# 21-RGMII_ETHERNET_PHY_-_ICSSG_PRG2_PRU1.net
KiCad netlist of a schematic drawn in Altium Designer
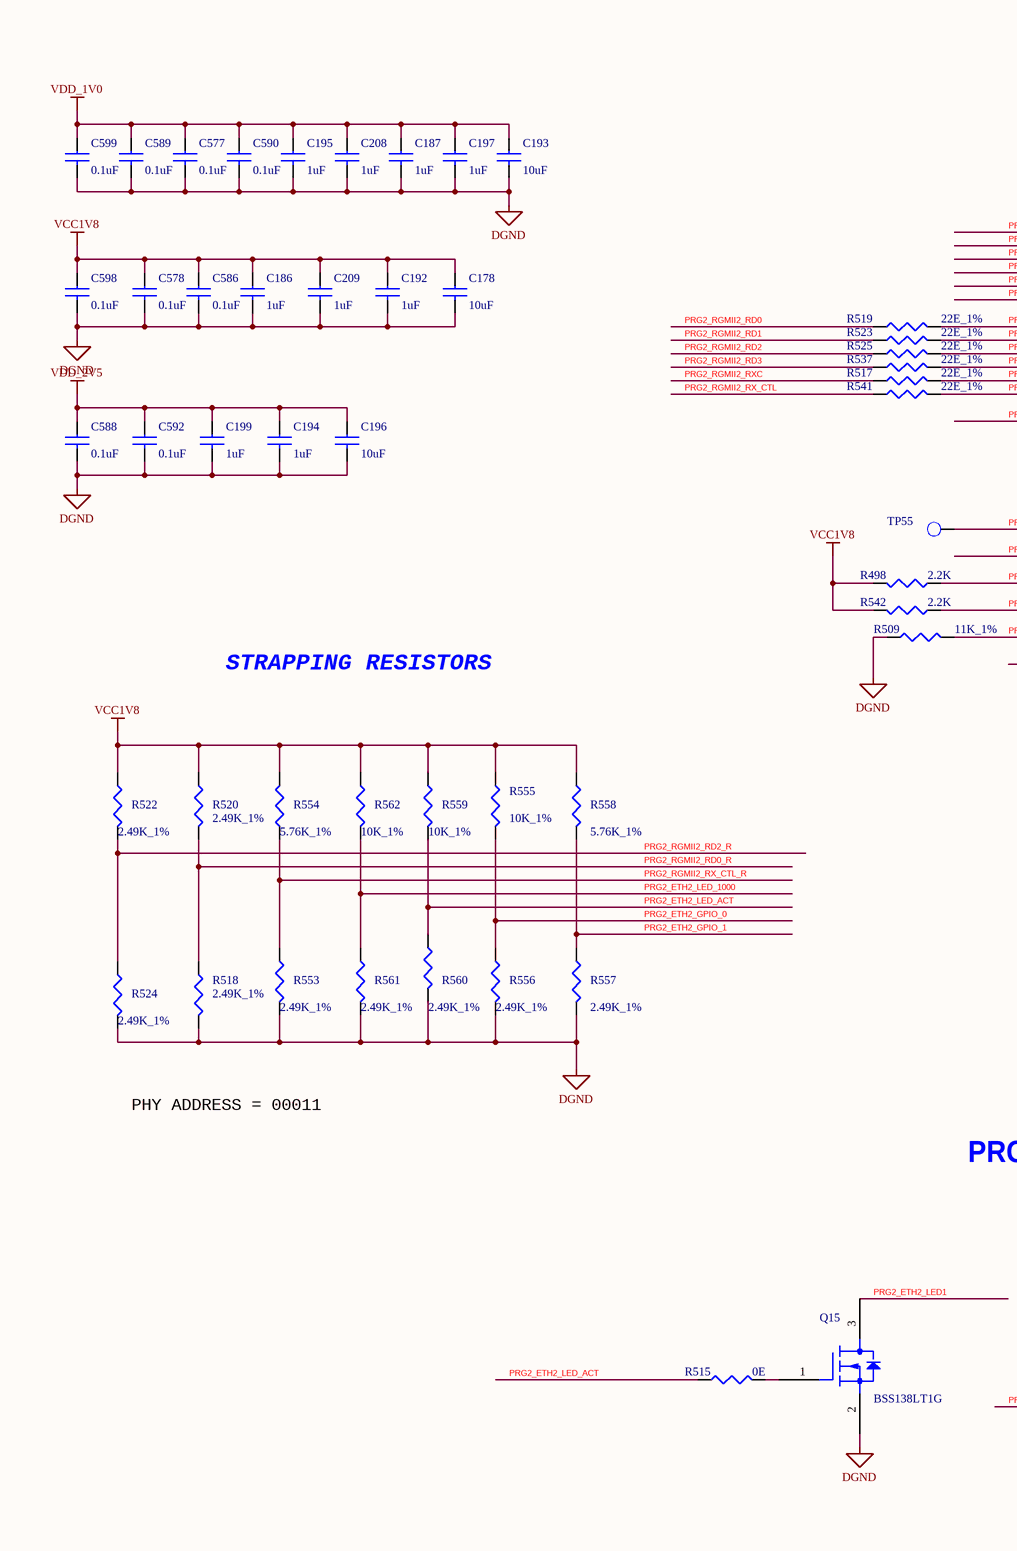
[diagram p0: 21-RGMII ETHERNET PHY - ICSSG PRG2_PRU1.SchDoc, left]
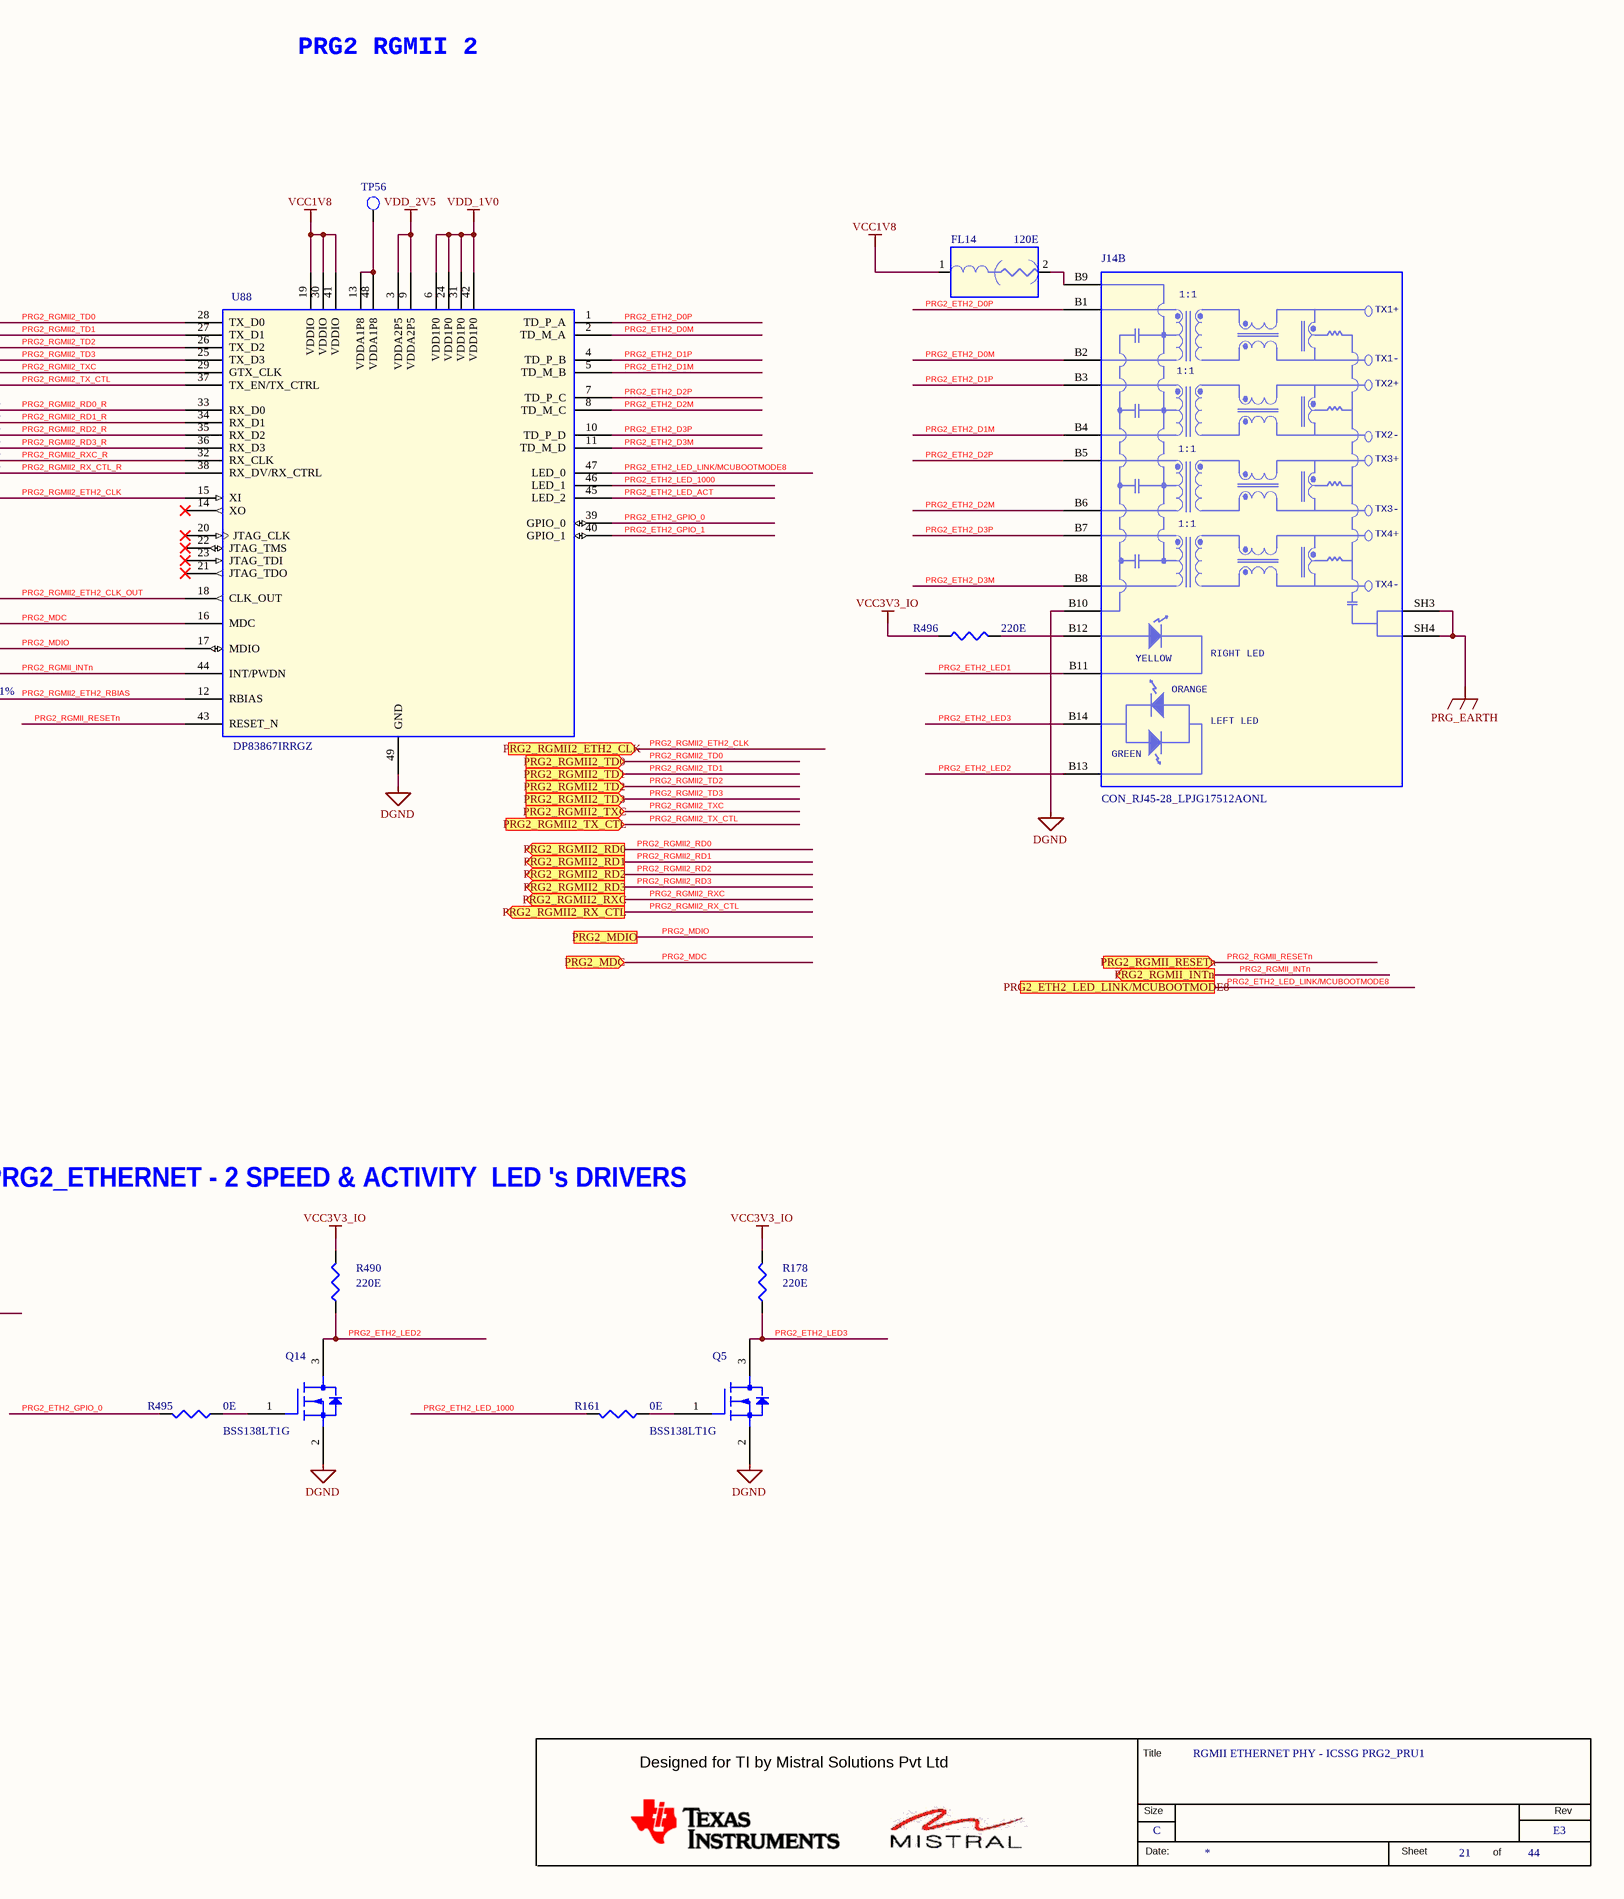
[diagram p1: 21-RGMII ETHERNET PHY - ICSSG PRG2_PRU1.SchDoc, right]

(export (version "E")
  (design (tool "Eeschema 10.0.6"))
  (components
    (comp (ref "C178")
      (value "10uF")
      (footprint "CAP0603_1")
      (description "CAP CERAMIC 10uF 10V 10% X5R 0603")
      (fields (field (name "DISTRIBUTOR_PART_NUMBER") "478-10766-1-ND") (field (name "VOLTAGE") "10V"))
      (libsource (lib "*") (part "CAP_Dup5"))
    )
    (comp (ref "C186")
      (value "1uF")
      (footprint "CAP0402_0-75")
      (description "CAP CERAMIC 1uF 16V 20% X5R 0402")
      (fields (field (name "DISTRIBUTOR_PART_NUMBER") "587-5514-1-ND") (field (name "VOLTAGE") "16V"))
      (libsource (lib "*") (part "CAP_Dup5"))
    )
    (comp (ref "C187")
      (value "1uF")
      (footprint "CAP0402_0-75")
      (description "CAP CERAMIC 1uF 16V 20% X5R 0402")
      (fields
        (field (name "MISTRAL PART NO") "120018020006-R")
        (field (name "MFR_PART_NUMBER") "EMK105BJ105MV-F")
      )
      (libsource (lib "*") (part "CAP_Dup5"))
    )
    (comp (ref "C192")
      (value "1uF")
      (footprint "CAP0402_0-75")
      (description "CAP CERAMIC 1uF 16V 20% X5R 0402")
      (fields (field (name "DISTRIBUTOR_PART_NUMBER") "587-5514-1-ND") (field (name "VOLTAGE") "16V"))
      (libsource (lib "*") (part "CAP_Dup5"))
    )
    (comp (ref "C193")
      (value "10uF")
      (footprint "CAP0603_1")
      (description "CAP CERAMIC 10uF 10V 10% X5R 0603")
      (fields
        (field (name "MISTRAL PART NO") "120010080001-R")
        (field (name "MFR_PART_NUMBER") "0603ZD106KAT2A")
      )
      (libsource (lib "*") (part "CAP_Dup5"))
    )
    (comp (ref "C194")
      (value "1uF")
      (footprint "CAP0402_0-75")
      (description "CAP CERAMIC 1uF 16V 20% X5R 0402")
      (fields
        (field (name "MISTRAL PART NO") "120018020006-R")
        (field (name "MFR_PART_NUMBER") "EMK105BJ105MV-F")
      )
      (libsource (lib "*") (part "CAP_Dup5"))
    )
    (comp (ref "C195")
      (value "1uF")
      (footprint "CAP0402_0-75")
      (description "CAP CERAMIC 1uF 16V 20% X5R 0402")
      (fields
        (field (name "MISTRAL PART NO") "120018020006-R")
        (field (name "MFR_PART_NUMBER") "EMK105BJ105MV-F")
      )
      (libsource (lib "*") (part "CAP_Dup5"))
    )
    (comp (ref "C196")
      (value "10uF")
      (footprint "CAP0603_1")
      (description "CAP CERAMIC 10uF 10V 10% X5R 0603")
      (fields
        (field (name "MISTRAL PART NO") "120010080001-R")
        (field (name "MFR_PART_NUMBER") "0603ZD106KAT2A")
      )
      (libsource (lib "*") (part "CAP_Dup5"))
    )
    (comp (ref "C197")
      (value "1uF")
      (footprint "CAP0402_0-75")
      (description "CAP CERAMIC 1uF 16V 20% X5R 0402")
      (fields (field (name "DISTRIBUTOR_PART_NUMBER") "587-5514-1-ND") (field (name "VOLTAGE") "16V"))
      (libsource (lib "*") (part "CAP_Dup5"))
    )
    (comp (ref "C199")
      (value "1uF")
      (footprint "CAP0402_0-75")
      (description "CAP CERAMIC 1uF 16V 20% X5R 0402")
      (fields
        (field (name "MISTRAL PART NO") "120018020006-R")
        (field (name "MFR_PART_NUMBER") "EMK105BJ105MV-F")
      )
      (libsource (lib "*") (part "CAP_Dup5"))
    )
    (comp (ref "C208")
      (value "1uF")
      (footprint "CAP0402_0-75")
      (description "CAP CERAMIC 1uF 16V 20% X5R 0402")
      (fields (field (name "DISTRIBUTOR_PART_NUMBER") "587-5514-1-ND") (field (name "VOLTAGE") "16V"))
      (libsource (lib "*") (part "CAP_Dup5"))
    )
    (comp (ref "C209")
      (value "1uF")
      (footprint "CAP0402_0-75")
      (description "CAP CERAMIC 1uF 16V 20% X5R 0402")
      (fields (field (name "DISTRIBUTOR_PART_NUMBER") "587-5514-1-ND") (field (name "VOLTAGE") "16V"))
      (libsource (lib "*") (part "CAP_Dup5"))
    )
    (comp (ref "C577")
      (value "0.1uF")
      (footprint "CAP0201_0-5")
      (description "CAP CERAMIC 0.1uF 16V 10% X5R 0201")
      (fields (field (name "DISTRIBUTOR_PART_NUMBER") "490-16742-1-ND") (field (name "VOLTAGE") "16V"))
      (libsource (lib "*") (part "CAP_Dup5"))
    )
    (comp (ref "C578")
      (value "0.1uF")
      (footprint "CAP0201_0-5")
      (description "CAP CERAMIC 0.1uF 16V 10% X5R 0201")
      (fields (field (name "DISTRIBUTOR_PART_NUMBER") "490-16742-1-ND") (field (name "VOLTAGE") "16V"))
      (libsource (lib "*") (part "CAP_Dup5"))
    )
    (comp (ref "C586")
      (value "0.1uF")
      (footprint "CAP0201_0-5")
      (description "CAP CERAMIC 0.1uF 16V 10% X5R 0201")
      (fields (field (name "DISTRIBUTOR_PART_NUMBER") "490-16742-1-ND") (field (name "VOLTAGE") "16V"))
      (libsource (lib "*") (part "CAP_Dup5"))
    )
    (comp (ref "C588")
      (value "0.1uF")
      (footprint "CAP0201_0-5")
      (description "CAP CERAMIC 0.1uF 16V 10% X5R 0201")
      (fields
        (field (name "MISTRAL PART NO") "120009030072-R")
        (field (name "MFR_PART_NUMBER") "GRM033R61C104KE84J")
      )
      (libsource (lib "*") (part "CAP_Dup5"))
    )
    (comp (ref "C589")
      (value "0.1uF")
      (footprint "CAP0201_0-5")
      (description "CAP CERAMIC 0.1uF 16V 10% X5R 0201")
      (fields
        (field (name "MISTRAL PART NO") "120009030072-R")
        (field (name "MFR_PART_NUMBER") "GRM033R61C104KE84J")
      )
      (libsource (lib "*") (part "CAP_Dup5"))
    )
    (comp (ref "C590")
      (value "0.1uF")
      (footprint "CAP0201_0-5")
      (description "CAP CERAMIC 0.1uF 16V 10% X5R 0201")
      (fields (field (name "DISTRIBUTOR_PART_NUMBER") "490-16742-1-ND") (field (name "VOLTAGE") "16V"))
      (libsource (lib "*") (part "CAP_Dup5"))
    )
    (comp (ref "C592")
      (value "0.1uF")
      (footprint "CAP0201_0-5")
      (description "CAP CERAMIC 0.1uF 16V 10% X5R 0201")
      (fields (field (name "DISTRIBUTOR_PART_NUMBER") "490-16742-1-ND") (field (name "VOLTAGE") "16V"))
      (libsource (lib "*") (part "CAP_Dup5"))
    )
    (comp (ref "C598")
      (value "0.1uF")
      (footprint "CAP0201_0-5")
      (description "CAP CERAMIC 0.1uF 16V 10% X5R 0201")
      (fields (field (name "DISTRIBUTOR_PART_NUMBER") "490-16742-1-ND") (field (name "VOLTAGE") "16V"))
      (libsource (lib "*") (part "CAP_Dup5"))
    )
    (comp (ref "C599")
      (value "0.1uF")
      (footprint "CAP0201_0-5")
      (description "CAP CERAMIC 0.1uF 16V 10% X5R 0201")
      (fields
        (field (name "MISTRAL PART NO") "120009030072-R")
        (field (name "MFR_PART_NUMBER") "GRM033R61C104KE84J")
      )
      (libsource (lib "*") (part "CAP_Dup5"))
    )
    (comp (ref "FL14")
      (value "120E")
      (footprint "EMIFIL_BLM15A_0402_0-6")
      (description "FERRITE CHIP 120E 1.3A 0402")
      (fields (field (name "DISTRIBUTOR_PART_NUMBER") "490-5203-1-ND") (field (name "VOLTAGE") "NA"))
      (libsource (lib "*") (part "EMIFILTER_IND"))
    )
    (comp (ref "J14")
      (value "CON_RJ45-28_LPJG17512AONL")
      (footprint "CON_RJ45-28_LPJG17512_S_R_T_25-3")
      (description "CON JACK RJ45 28POS REGISTERED FEMALE RA TH")
      (fields
        (field (name "MISTRAL PART NO") "150017080001-R")
        (field (name "MFR_PART_NUMBER") "LPJG17512AONL")
      )
      (libsource (lib "*") (part "CON_RJ45-28_LPJG17512AONL"))
    )
    (comp (ref "Q5")
      (value "BSS138LT1G")
      (footprint "SOT23-123")
      (description "IC MOSFET N-CHANNEL 50V, SOT23-3")
      (fields (field (name "DISTRIBUTOR_PART_NUMBER") "863-BSS138LT1G") (field (name "VOLTAGE") "50V"))
      (libsource (lib "*") (part "MOSFET_BSS138LT1G"))
    )
    (comp (ref "Q14")
      (value "BSS138LT1G")
      (footprint "SOT23-123")
      (description "IC MOSFET N-CHANNEL 50V, SOT23-3")
      (fields (field (name "MISTRAL PART NO") "142016040001-R") (field (name "TOLERANCE") "NA"))
      (libsource (lib "*") (part "MOSFET_BSS138LT1G"))
    )
    (comp (ref "Q15")
      (value "BSS138LT1G")
      (footprint "SOT23-123")
      (description "IC MOSFET N-CHANNEL 50V, SOT23-3")
      (fields (field (name "DISTRIBUTOR_PART_NUMBER") "863-BSS138LT1G") (field (name "VOLTAGE") "50V"))
      (libsource (lib "*") (part "MOSFET_BSS138LT1G"))
    )
    (comp (ref "R161")
      (value "0E")
      (footprint "RES0402_0-5")
      (description "RES 0E 1/16W 0402")
      (fields (field (name "DISTRIBUTOR_PART_NUMBER") "541-0.0JCT-ND") (field (name "VOLTAGE") "NA"))
      (libsource (lib "*") (part "RESISTOR_Dup4"))
    )
    (comp (ref "R178")
      (value "220E")
      (footprint "RES0402_0-5")
      (description "RES 220E 1/16W 5% 0402")
      (fields (field (name "VOLTAGE") "NA") (field (name "DISTRIBUTOR_PART_NUMBER") "P220JCT-ND"))
      (libsource (lib "*") (part "RESISTOR_Dup5"))
    )
    (comp (ref "R490")
      (value "220E")
      (footprint "RES0402_0-5")
      (description "RES 220E 1/16W 5% 0402")
      (fields (field (name "VOLTAGE") "NA") (field (name "MISTRAL PART NO") "110009030506-R"))
      (libsource (lib "*") (part "RESISTOR_Dup5"))
    )
    (comp (ref "R495")
      (value "0E")
      (footprint "RES0402_0-5")
      (description "RES 0E 1/16W 0402")
      (fields
        (field (name "MISTRAL PART NO") "110010080019-P")
        (field (name "MFR_PART_NUMBER") "CRCW04020000Z0ED")
      )
      (libsource (lib "*") (part "RESISTOR_Dup4"))
    )
    (comp (ref "R496")
      (value "220E")
      (footprint "RES0402_0-5")
      (description "RES 220E 1/16W 5% 0402")
      (fields (field (name "VOLTAGE") "NA") (field (name "DISTRIBUTOR_PART_NUMBER") "P220JCT-ND"))
      (libsource (lib "*") (part "RESISTOR_Dup5"))
    )
    (comp (ref "R498")
      (value "2.2K")
      (footprint "RES0402_0-5")
      (description "RES 2.2K 1/16W 5% 0402")
      (fields (field (name "DISTRIBUTOR_PART_NUMBER") "311-2.2KJRCT-ND") (field (name "VOLTAGE") "NA"))
      (libsource (lib "*") (part "RESISTOR_Dup5"))
    )
    (comp (ref "R509")
      (value "11K_1%")
      (footprint "RES0402_0-5")
      (description "RES 11K 1/16W 1% 0402")
      (fields (field (name "DISTRIBUTOR_PART_NUMBER") "311-11.0KLRCT-ND") (field (name "VOLTAGE") "NA"))
      (libsource (lib "*") (part "RESISTOR_Dup5"))
    )
    (comp (ref "R515")
      (value "0E")
      (footprint "RES0402_0-5")
      (description "RES 0E 1/16W 0402")
      (fields (field (name "DISTRIBUTOR_PART_NUMBER") "541-0.0JCT-ND") (field (name "VOLTAGE") "NA"))
      (libsource (lib "*") (part "RESISTOR_Dup4"))
    )
    (comp (ref "R517")
      (value "22E_1%")
      (footprint "RES0402")
      (description "RES 22E 1/16W 1% 0402")
      (fields
        (field (name "MISTRAL PART NO") "110009090004-P")
        (field (name "MFR_PART_NUMBER") "RC0402FR-0722RL")
      )
      (libsource (lib "*") (part "RESISTOR_Dup5"))
    )
    (comp (ref "R518")
      (value "2.49K_1%")
      (footprint "RES0402")
      (description "RES 2.49K 1/16W 1% 0402")
      (fields (field (name "DISTRIBUTOR_PART_NUMBER") "311-2.49KLRCT-ND") (field (name "VOLTAGE") "NA"))
      (libsource (lib "*") (part "RESISTOR_Dup5"))
    )
    (comp (ref "R519")
      (value "22E_1%")
      (footprint "RES0402")
      (description "RES 22E 1/16W 1% 0402")
      (fields
        (field (name "CUST_PART_NUMBER") "4700-80047E")
        (field (name "DISTRIBUTOR_PART_NUMBER") "311-22.0LRCT-ND")
      )
      (libsource (lib "*") (part "RESISTOR_Dup5"))
    )
    (comp (ref "R520")
      (value "2.49K_1%")
      (footprint "RES0402")
      (description "RES 2.49K 1/16W 1% 0402")
      (fields
        (field (name "MISTRAL PART NO") "110016050020-R")
        (field (name "MFR_PART_NUMBER") "RC0402FR-072K49L")
      )
      (libsource (lib "*") (part "RESISTOR_Dup5"))
    )
    (comp (ref "R522")
      (value "2.49K_1%")
      (footprint "RES0402")
      (description "RES 2.49K 1/16W 1% 0402")
      (fields (field (name "DISTRIBUTOR_PART_NUMBER") "311-2.49KLRCT-ND") (field (name "VOLTAGE") "NA"))
      (libsource (lib "*") (part "RESISTOR_Dup5"))
    )
    (comp (ref "R523")
      (value "22E_1%")
      (footprint "RES0402")
      (description "RES 22E 1/16W 1% 0402")
      (fields
        (field (name "MISTRAL PART NO") "110009090004-P")
        (field (name "MFR_PART_NUMBER") "RC0402FR-0722RL")
      )
      (libsource (lib "*") (part "RESISTOR_Dup5"))
    )
    (comp (ref "R524")
      (value "2.49K_1%")
      (footprint "RES0402")
      (description "RES 2.49K 1/16W 1% 0402")
      (fields (field (name "DISTRIBUTOR_PART_NUMBER") "311-2.49KLRCT-ND") (field (name "VOLTAGE") "NA"))
      (libsource (lib "*") (part "RESISTOR_Dup5"))
    )
    (comp (ref "R525")
      (value "22E_1%")
      (footprint "RES0402")
      (description "RES 22E 1/16W 1% 0402")
      (fields
        (field (name "CUST_PART_NUMBER") "4700-80047E")
        (field (name "DISTRIBUTOR_PART_NUMBER") "311-22.0LRCT-ND")
      )
      (libsource (lib "*") (part "RESISTOR_Dup5"))
    )
    (comp (ref "R537")
      (value "22E_1%")
      (footprint "RES0402")
      (description "RES 22E 1/16W 1% 0402")
      (fields
        (field (name "MISTRAL PART NO") "110009090004-P")
        (field (name "MFR_PART_NUMBER") "RC0402FR-0722RL")
      )
      (libsource (lib "*") (part "RESISTOR_Dup5"))
    )
    (comp (ref "R541")
      (value "22E_1%")
      (footprint "RES0402")
      (description "RES 22E 1/16W 1% 0402")
      (fields
        (field (name "CUST_PART_NUMBER") "4700-80047E")
        (field (name "DISTRIBUTOR_PART_NUMBER") "311-22.0LRCT-ND")
      )
      (libsource (lib "*") (part "RESISTOR_Dup5"))
    )
    (comp (ref "R542")
      (value "2.2K")
      (footprint "RES0402_0-5")
      (description "RES 2.2K 1/16W 5% 0402")
      (fields
        (field (name "MISTRAL PART NO") "110010120018-R")
        (field (name "MFR_PART_NUMBER") "RC0402JR-072K2L")
      )
      (libsource (lib "*") (part "RESISTOR_Dup5"))
    )
    (comp (ref "R553")
      (value "2.49K_1%")
      (footprint "RES0402")
      (description "RES 2.49K 1/16W 1% 0402")
      (fields (field (name "DISTRIBUTOR_PART_NUMBER") "311-2.49KLRCT-ND") (field (name "VOLTAGE") "NA"))
      (libsource (lib "*") (part "RESISTOR_Dup5"))
    )
    (comp (ref "R554")
      (value "5.76K_1%")
      (footprint "RES0402")
      (description "RES 5.76K 1/10W 1% 0402")
      (fields
        (field (name "MISTRAL PART NO") "110009030945-R")
        (field (name "MFR_PART_NUMBER") "ERJ-2RKF5761X")
      )
      (libsource (lib "*") (part "RESISTOR_Dup5"))
    )
    (comp (ref "R555")
      (value "10K_1%")
      (footprint "RES0402_0-5")
      (description "RES 10K 1/16W 1% 0402")
      (fields
        (field (name "MISTRAL PART NO") "110009030220-P")
        (field (name "MFR_PART_NUMBER") "RC0402FR-0710KL")
      )
      (libsource (lib "*") (part "RESISTOR_Dup5"))
    )
    (comp (ref "R556")
      (value "2.49K_1%")
      (footprint "RES0402")
      (description "RES 2.49K 1/16W 1% 0402")
      (fields
        (field (name "MISTRAL PART NO") "110016050020-R")
        (field (name "MFR_PART_NUMBER") "RC0402FR-072K49L")
      )
      (libsource (lib "*") (part "RESISTOR_Dup5"))
    )
    (comp (ref "R557")
      (value "2.49K_1%")
      (footprint "RES0402")
      (description "RES 2.49K 1/16W 1% 0402")
      (fields
        (field (name "MISTRAL PART NO") "110016050020-R")
        (field (name "MFR_PART_NUMBER") "RC0402FR-072K49L")
      )
      (libsource (lib "*") (part "RESISTOR_Dup5"))
    )
    (comp (ref "R558")
      (value "5.76K_1%")
      (footprint "RES0402")
      (description "RES 5.76K 1/10W 1% 0402")
      (fields (field (name "DISTRIBUTOR_PART_NUMBER") "P5.76KLCT-ND") (field (name "TOLERANCE") "1%"))
      (libsource (lib "*") (part "RESISTOR_Dup5"))
    )
    (comp (ref "R559")
      (value "10K_1%")
      (footprint "RES0402_0-5")
      (description "RES 10K 1/16W 1% 0402")
      (fields (field (name "DISTRIBUTOR_PART_NUMBER") "311-10.0KLRTR-ND") (field (name "VOLTAGE") "NA"))
      (libsource (lib "*") (part "RESISTOR_Dup5"))
    )
    (comp (ref "R560")
      (value "2.49K_1%")
      (footprint "RES0402")
      (description "RES 2.49K 1/16W 1% 0402")
      (fields (field (name "DISTRIBUTOR_PART_NUMBER") "311-2.49KLRCT-ND") (field (name "VOLTAGE") "NA"))
      (libsource (lib "*") (part "RESISTOR_Dup5"))
    )
    (comp (ref "R561")
      (value "2.49K_1%")
      (footprint "RES0402")
      (description "RES 2.49K 1/16W 1% 0402")
      (fields
        (field (name "MISTRAL PART NO") "110016050020-R")
        (field (name "MFR_PART_NUMBER") "RC0402FR-072K49L")
      )
      (libsource (lib "*") (part "RESISTOR_Dup5"))
    )
    (comp (ref "R562")
      (value "10K_1%")
      (footprint "RES0402_0-5")
      (description "RES 10K 1/16W 1% 0402")
      (fields (field (name "DISTRIBUTOR_PART_NUMBER") "311-10.0KLRTR-ND") (field (name "VOLTAGE") "NA"))
      (libsource (lib "*") (part "RESISTOR_Dup5"))
    )
    (comp (ref "TP55")
      (value "TP40_SMD")
      (footprint "TP40_SMD")
      (description "TESTPOINT CIR 40 SMD")
      (fields (field (name "VOLTAGE") "NA") (field (name "MISTRAL PART NO") "130009030933"))
      (libsource (lib "*") (part "TESTPOINT"))
    )
    (comp (ref "TP56")
      (value "TP40_SMD")
      (footprint "TP40_SMD")
      (description "TESTPOINT CIR 40 SMD")
      (fields (field (name "MISTRAL PART NO") "130009030933") (field (name "DISTRIBUTOR_PART_NUMBER") "NA"))
      (libsource (lib "*") (part "TESTPOINT"))
    )
    (comp (ref "U88")
      (value "DP83867IRRGZ")
      (footprint "QFN48_19-68_280X280_1")
      (description "IC HIGH IMMUNITY 10/100/1000 Mb/s ETHERNET PHY LAYER TRANSCEIVER VQFN48")
      (fields (field (name "MISTRAL PART NO") "143017080002-R") (field (name "TOLERANCE") "NA"))
      (libsource (lib "*") (part "DP83867IRRGZ_VQFN48"))
    )
  )
  (nets
    (net (code "1") (name "/PRG2_ETH2_D0M") (class "Default")
      (node (ref "J14") (pin "B2") (pinfunction "TD1-_2_B2") (pintype "passive"))
      (node (ref "U88") (pin "2") (pinfunction "TD_M_A_2") (pintype "passive"))
    )
    (net (code "2") (name "/PRG2_ETH2_D0P") (class "Default")
      (node (ref "J14") (pin "B1") (pinfunction "TD1+_2_B1") (pintype "passive"))
      (node (ref "U88") (pin "1") (pinfunction "TD_P_A_1") (pintype "passive"))
    )
    (net (code "3") (name "/PRG2_ETH2_D1M") (class "Default")
      (node (ref "J14") (pin "B4") (pinfunction "TD2-_2_B4") (pintype "passive"))
      (node (ref "U88") (pin "5") (pinfunction "TD_M_B_5") (pintype "passive"))
    )
    (net (code "4") (name "/PRG2_ETH2_D1P") (class "Default")
      (node (ref "J14") (pin "B3") (pinfunction "TD2+_2_B3") (pintype "passive"))
      (node (ref "U88") (pin "4") (pinfunction "TD_P_B_4") (pintype "passive"))
    )
    (net (code "5") (name "/PRG2_ETH2_D2M") (class "Default")
      (node (ref "J14") (pin "B6") (pinfunction "TD3-_2_B6") (pintype "passive"))
      (node (ref "U88") (pin "8") (pinfunction "TD_M_C_8") (pintype "passive"))
    )
    (net (code "6") (name "/PRG2_ETH2_D2P") (class "Default")
      (node (ref "J14") (pin "B5") (pinfunction "TD3+_2_B5") (pintype "passive"))
      (node (ref "U88") (pin "7") (pinfunction "TD_P_C_7") (pintype "passive"))
    )
    (net (code "7") (name "/PRG2_ETH2_D3M") (class "Default")
      (node (ref "J14") (pin "B8") (pinfunction "TD4-_2_B8") (pintype "passive"))
      (node (ref "U88") (pin "11") (pinfunction "TD_M_D_11") (pintype "passive"))
    )
    (net (code "8") (name "/PRG2_ETH2_D3P") (class "Default")
      (node (ref "J14") (pin "B7") (pinfunction "TD4+_2_B7") (pintype "passive"))
      (node (ref "U88") (pin "10") (pinfunction "TD_P_D_10") (pintype "passive"))
    )
    (net (code "9") (name "/PRG2_ETH2_GPIO_0") (class "Default")
      (node (ref "R495") (pin "2") (pinfunction "2_2") (pintype "passive"))
      (node (ref "R555") (pin "2") (pinfunction "2_2") (pintype "passive"))
      (node (ref "R556") (pin "1") (pinfunction "1_1") (pintype "passive"))
      (node (ref "U88") (pin "39") (pinfunction "GPIO_0_39") (pintype "bidirectional"))
    )
    (net (code "10") (name "/PRG2_ETH2_GPIO_1") (class "Default")
      (node (ref "R557") (pin "1") (pinfunction "1_1") (pintype "passive"))
      (node (ref "R558") (pin "2") (pinfunction "2_2") (pintype "passive"))
      (node (ref "U88") (pin "40") (pinfunction "GPIO_1_40") (pintype "bidirectional"))
    )
    (net (code "11") (name "/PRG2_ETH2_LED1") (class "Default")
      (node (ref "J14") (pin "B11") (pinfunction "B11_B11") (pintype "passive"))
      (node (ref "Q15") (pin "3") (pinfunction "D_3") (pintype "passive"))
    )
    (net (code "12") (name "/PRG2_ETH2_LED2") (class "Default")
      (node (ref "J14") (pin "B13") (pinfunction "B13_B13") (pintype "passive"))
      (node (ref "Q14") (pin "3") (pinfunction "D_3") (pintype "passive"))
      (node (ref "R490") (pin "1") (pinfunction "1_1") (pintype "passive"))
    )
    (net (code "13") (name "/PRG2_ETH2_LED3") (class "Default")
      (node (ref "J14") (pin "B14") (pinfunction "B14_B14") (pintype "passive"))
      (node (ref "Q5") (pin "3") (pinfunction "D_3") (pintype "passive"))
      (node (ref "R178") (pin "1") (pinfunction "1_1") (pintype "passive"))
    )
    (net (code "14") (name "/PRG2_ETH2_LED_1000") (class "Default")
      (node (ref "R161") (pin "2") (pinfunction "2_2") (pintype "passive"))
      (node (ref "R561") (pin "1") (pinfunction "1_1") (pintype "passive"))
      (node (ref "R562") (pin "2") (pinfunction "2_2") (pintype "passive"))
      (node (ref "U88") (pin "46") (pinfunction "LED_1_46") (pintype "passive"))
    )
    (net (code "15") (name "/PRG2_ETH2_LED_ACT") (class "Default")
      (node (ref "R515") (pin "1") (pinfunction "1_1") (pintype "passive"))
      (node (ref "R559") (pin "2") (pinfunction "2_2") (pintype "passive"))
      (node (ref "R560") (pin "1") (pinfunction "1_1") (pintype "passive"))
      (node (ref "U88") (pin "45") (pinfunction "LED_2_45") (pintype "passive"))
    )
    (net (code "16") (name "/PRG2_ETH2_LED_LINK{slash}MCUBOOTMODE8") (class "Default")
      (node (ref "U88") (pin "47") (pinfunction "LED_0_47") (pintype "passive"))
    )
    (net (code "17") (name "/PRG2_MDC") (class "Default")
      (node (ref "U88") (pin "16") (pinfunction "MDC_16") (pintype "passive"))
    )
    (net (code "18") (name "/PRG2_MDIO") (class "Default")
      (node (ref "R498") (pin "1") (pinfunction "1_1") (pintype "passive"))
      (node (ref "U88") (pin "17") (pinfunction "MDIO_17") (pintype "bidirectional"))
    )
    (net (code "19") (name "/PRG2_RGMII2_ETH2_CLK") (class "Default")
      (node (ref "U88") (pin "15") (pinfunction "XI_15") (pintype "input"))
    )
    (net (code "20") (name "/PRG2_RGMII2_ETH2_CLK_OUT") (class "Default")
      (node (ref "TP55") (pin "1") (pinfunction "TP_1") (pintype "passive"))
      (node (ref "U88") (pin "18") (pinfunction "CLK_OUT_18") (pintype "output"))
    )
    (net (code "21") (name "/PRG2_RGMII2_ETH2_RBIAS") (class "Default")
      (node (ref "R509") (pin "1") (pinfunction "1_1") (pintype "passive"))
      (node (ref "U88") (pin "12") (pinfunction "RBIAS_12") (pintype "passive"))
    )
    (net (code "22") (name "/PRG2_RGMII2_RD0") (class "Default")
      (node (ref "R519") (pin "1") (pinfunction "1_1") (pintype "passive"))
    )
    (net (code "23") (name "/PRG2_RGMII2_RD0_R") (class "Default")
      (node (ref "R518") (pin "1") (pinfunction "1_1") (pintype "passive"))
      (node (ref "R519") (pin "2") (pinfunction "2_2") (pintype "passive"))
      (node (ref "R520") (pin "2") (pinfunction "2_2") (pintype "passive"))
      (node (ref "U88") (pin "33") (pinfunction "RX_D0_33") (pintype "passive"))
    )
    (net (code "24") (name "/PRG2_RGMII2_RD1") (class "Default")
      (node (ref "R523") (pin "1") (pinfunction "1_1") (pintype "passive"))
    )
    (net (code "25") (name "/PRG2_RGMII2_RD1_R") (class "Default")
      (node (ref "R523") (pin "2") (pinfunction "2_2") (pintype "passive"))
      (node (ref "U88") (pin "34") (pinfunction "RX_D1_34") (pintype "passive"))
    )
    (net (code "26") (name "/PRG2_RGMII2_RD2") (class "Default")
      (node (ref "R525") (pin "1") (pinfunction "1_1") (pintype "passive"))
    )
    (net (code "27") (name "/PRG2_RGMII2_RD2_R") (class "Default")
      (node (ref "R522") (pin "2") (pinfunction "2_2") (pintype "passive"))
      (node (ref "R524") (pin "1") (pinfunction "1_1") (pintype "passive"))
      (node (ref "R525") (pin "2") (pinfunction "2_2") (pintype "passive"))
      (node (ref "U88") (pin "35") (pinfunction "RX_D2_35") (pintype "passive"))
    )
    (net (code "28") (name "/PRG2_RGMII2_RD3") (class "Default")
      (node (ref "R537") (pin "1") (pinfunction "1_1") (pintype "passive"))
    )
    (net (code "29") (name "/PRG2_RGMII2_RD3_R") (class "Default")
      (node (ref "R537") (pin "2") (pinfunction "2_2") (pintype "passive"))
      (node (ref "U88") (pin "36") (pinfunction "RX_D3_36") (pintype "passive"))
    )
    (net (code "30") (name "/PRG2_RGMII2_RXC") (class "Default")
      (node (ref "R517") (pin "1") (pinfunction "1_1") (pintype "passive"))
    )
    (net (code "31") (name "/PRG2_RGMII2_RXC_R") (class "Default")
      (node (ref "R517") (pin "2") (pinfunction "2_2") (pintype "passive"))
      (node (ref "U88") (pin "32") (pinfunction "RX_CLK_32") (pintype "passive"))
    )
    (net (code "32") (name "/PRG2_RGMII2_RX_CTL") (class "Default")
      (node (ref "R541") (pin "1") (pinfunction "1_1") (pintype "passive"))
    )
    (net (code "33") (name "/PRG2_RGMII2_RX_CTL_R") (class "Default")
      (node (ref "R541") (pin "2") (pinfunction "2_2") (pintype "passive"))
      (node (ref "R553") (pin "1") (pinfunction "1_1") (pintype "passive"))
      (node (ref "R554") (pin "1") (pinfunction "1_1") (pintype "passive"))
      (node (ref "U88") (pin "38") (pinfunction "RX_DV/RX_CTRL_38") (pintype "passive"))
    )
    (net (code "34") (name "/PRG2_RGMII2_TD0") (class "Default")
      (node (ref "U88") (pin "28") (pinfunction "TX_D0_28") (pintype "passive"))
    )
    (net (code "35") (name "/PRG2_RGMII2_TD1") (class "Default")
      (node (ref "U88") (pin "27") (pinfunction "TX_D1_27") (pintype "passive"))
    )
    (net (code "36") (name "/PRG2_RGMII2_TD2") (class "Default")
      (node (ref "U88") (pin "26") (pinfunction "TX_D2_26") (pintype "passive"))
    )
    (net (code "37") (name "/PRG2_RGMII2_TD3") (class "Default")
      (node (ref "U88") (pin "25") (pinfunction "TX_D3_25") (pintype "passive"))
    )
    (net (code "38") (name "/PRG2_RGMII2_TXC") (class "Default")
      (node (ref "U88") (pin "29") (pinfunction "GTX_CLK_29") (pintype "passive"))
    )
    (net (code "39") (name "/PRG2_RGMII2_TX_CTL") (class "Default")
      (node (ref "U88") (pin "37") (pinfunction "TX_EN/TX_CTRL_37") (pintype "passive"))
    )
    (net (code "40") (name "/PRG2_RGMII_INTn") (class "Default")
      (node (ref "R542") (pin "1") (pinfunction "1_1") (pintype "passive"))
      (node (ref "U88") (pin "44") (pinfunction "INT/PWDN_44") (pintype "passive"))
    )
    (net (code "41") (name "/PRG2_RGMII_RESETn") (class "Default")
      (node (ref "U88") (pin "43") (pinfunction "RESET_N_43") (pintype "passive"))
    )
    (net (code "42") (name "DGND") (class "Default")
      (node (ref "C178") (pin "2") (pinfunction "2_2") (pintype "passive"))
      (node (ref "C186") (pin "2") (pinfunction "2_2") (pintype "passive"))
      (node (ref "C187") (pin "2") (pinfunction "2_2") (pintype "passive"))
      (node (ref "C192") (pin "2") (pinfunction "2_2") (pintype "passive"))
      (node (ref "C193") (pin "2") (pinfunction "2_2") (pintype "passive"))
      (node (ref "C194") (pin "2") (pinfunction "2_2") (pintype "passive"))
      (node (ref "C195") (pin "2") (pinfunction "2_2") (pintype "passive"))
      (node (ref "C196") (pin "2") (pinfunction "2_2") (pintype "passive"))
      (node (ref "C197") (pin "2") (pinfunction "2_2") (pintype "passive"))
      (node (ref "C199") (pin "2") (pinfunction "2_2") (pintype "passive"))
      (node (ref "C208") (pin "2") (pinfunction "2_2") (pintype "passive"))
      (node (ref "C209") (pin "2") (pinfunction "2_2") (pintype "passive"))
      (node (ref "C577") (pin "2") (pinfunction "2_2") (pintype "passive"))
      (node (ref "C578") (pin "2") (pinfunction "2_2") (pintype "passive"))
      (node (ref "C586") (pin "2") (pinfunction "2_2") (pintype "passive"))
      (node (ref "C588") (pin "2") (pinfunction "2_2") (pintype "passive"))
      (node (ref "C589") (pin "2") (pinfunction "2_2") (pintype "passive"))
      (node (ref "C590") (pin "2") (pinfunction "2_2") (pintype "passive"))
      (node (ref "C592") (pin "2") (pinfunction "2_2") (pintype "passive"))
      (node (ref "C598") (pin "2") (pinfunction "2_2") (pintype "passive"))
      (node (ref "C599") (pin "2") (pinfunction "2_2") (pintype "passive"))
      (node (ref "J14") (pin "B10") (pinfunction "GND_B10") (pintype "power_in"))
      (node (ref "Q14") (pin "2") (pinfunction "S_2") (pintype "passive"))
      (node (ref "Q15") (pin "2") (pinfunction "S_2") (pintype "passive"))
      (node (ref "Q5") (pin "2") (pinfunction "S_2") (pintype "passive"))
      (node (ref "R509") (pin "2") (pinfunction "2_2") (pintype "passive"))
      (node (ref "R518") (pin "2") (pinfunction "2_2") (pintype "passive"))
      (node (ref "R524") (pin "2") (pinfunction "2_2") (pintype "passive"))
      (node (ref "R553") (pin "2") (pinfunction "2_2") (pintype "passive"))
      (node (ref "R556") (pin "2") (pinfunction "2_2") (pintype "passive"))
      (node (ref "R557") (pin "2") (pinfunction "2_2") (pintype "passive"))
      (node (ref "R560") (pin "2") (pinfunction "2_2") (pintype "passive"))
      (node (ref "R561") (pin "2") (pinfunction "2_2") (pintype "passive"))
      (node (ref "U88") (pin "49") (pinfunction "GND_49") (pintype "power_in"))
    )
    (net (code "43") (name "Net-(J14-PadB12)") (class "Default")
      (node (ref "J14") (pin "B12") (pinfunction "B12_B12") (pintype "passive"))
      (node (ref "R496") (pin "2") (pinfunction "2_2") (pintype "passive"))
    )
    (net (code "44") (name "Net-(J14B-VCC)") (class "Default")
      (node (ref "FL14") (pin "2") (pinfunction "2_2") (pintype "passive"))
      (node (ref "J14") (pin "B9") (pinfunction "VCC_B9") (pintype "power_in"))
    )
    (net (code "45") (name "Net-(Q5-G)") (class "Default")
      (node (ref "Q5") (pin "1") (pinfunction "G_1") (pintype "passive"))
      (node (ref "R161") (pin "1") (pinfunction "1_1") (pintype "passive"))
    )
    (net (code "46") (name "Net-(Q14-G)") (class "Default")
      (node (ref "Q14") (pin "1") (pinfunction "G_1") (pintype "passive"))
      (node (ref "R495") (pin "1") (pinfunction "1_1") (pintype "passive"))
    )
    (net (code "47") (name "Net-(Q15-G)") (class "Default")
      (node (ref "Q15") (pin "1") (pinfunction "G_1") (pintype "passive"))
      (node (ref "R515") (pin "2") (pinfunction "2_2") (pintype "passive"))
    )
    (net (code "48") (name "Net-(TP56-TP)") (class "Default")
      (node (ref "TP56") (pin "1") (pinfunction "TP_1") (pintype "passive"))
      (node (ref "U88") (pin "13") (pinfunction "VDDA1P8_13") (pintype "power_in"))
      (node (ref "U88") (pin "48") (pinfunction "VDDA1P8_48") (pintype "power_in"))
    )
    (net (code "49") (name "PRG_EARTH") (class "Default")
      (node (ref "J14") (pin "SH3") (pinfunction "SH3_SH3") (pintype "passive"))
      (node (ref "J14") (pin "SH4") (pinfunction "SH4_SH4") (pintype "passive"))
    )
    (net (code "50") (name "VCC1V8") (class "Default")
      (node (ref "C178") (pin "1") (pinfunction "1_1") (pintype "passive"))
      (node (ref "C186") (pin "1") (pinfunction "1_1") (pintype "passive"))
      (node (ref "C192") (pin "1") (pinfunction "1_1") (pintype "passive"))
      (node (ref "C209") (pin "1") (pinfunction "1_1") (pintype "passive"))
      (node (ref "C578") (pin "1") (pinfunction "1_1") (pintype "passive"))
      (node (ref "C586") (pin "1") (pinfunction "1_1") (pintype "passive"))
      (node (ref "C598") (pin "1") (pinfunction "1_1") (pintype "passive"))
      (node (ref "FL14") (pin "1") (pinfunction "1_1") (pintype "passive"))
      (node (ref "R498") (pin "2") (pinfunction "2_2") (pintype "passive"))
      (node (ref "R520") (pin "1") (pinfunction "1_1") (pintype "passive"))
      (node (ref "R522") (pin "1") (pinfunction "1_1") (pintype "passive"))
      (node (ref "R542") (pin "2") (pinfunction "2_2") (pintype "passive"))
      (node (ref "R554") (pin "2") (pinfunction "2_2") (pintype "passive"))
      (node (ref "R555") (pin "1") (pinfunction "1_1") (pintype "passive"))
      (node (ref "R558") (pin "1") (pinfunction "1_1") (pintype "passive"))
      (node (ref "R559") (pin "1") (pinfunction "1_1") (pintype "passive"))
      (node (ref "R562") (pin "1") (pinfunction "1_1") (pintype "passive"))
      (node (ref "U88") (pin "19") (pinfunction "VDDIO_19") (pintype "power_in"))
      (node (ref "U88") (pin "30") (pinfunction "VDDIO_30") (pintype "power_in"))
      (node (ref "U88") (pin "41") (pinfunction "VDDIO_41") (pintype "power_in"))
    )
    (net (code "51") (name "VCC3V3_IO") (class "Default")
      (node (ref "R178") (pin "2") (pinfunction "2_2") (pintype "passive"))
      (node (ref "R490") (pin "2") (pinfunction "2_2") (pintype "passive"))
      (node (ref "R496") (pin "1") (pinfunction "1_1") (pintype "passive"))
    )
    (net (code "52") (name "VDD_1V0") (class "Default")
      (node (ref "C187") (pin "1") (pinfunction "1_1") (pintype "passive"))
      (node (ref "C193") (pin "1") (pinfunction "1_1") (pintype "passive"))
      (node (ref "C195") (pin "1") (pinfunction "1_1") (pintype "passive"))
      (node (ref "C197") (pin "1") (pinfunction "1_1") (pintype "passive"))
      (node (ref "C208") (pin "1") (pinfunction "1_1") (pintype "passive"))
      (node (ref "C577") (pin "1") (pinfunction "1_1") (pintype "passive"))
      (node (ref "C589") (pin "1") (pinfunction "1_1") (pintype "passive"))
      (node (ref "C590") (pin "1") (pinfunction "1_1") (pintype "passive"))
      (node (ref "C599") (pin "1") (pinfunction "1_1") (pintype "passive"))
      (node (ref "U88") (pin "24") (pinfunction "VDD1P0_24") (pintype "power_in"))
      (node (ref "U88") (pin "31") (pinfunction "VDD1P0_31") (pintype "power_in"))
      (node (ref "U88") (pin "42") (pinfunction "VDD1P0_42") (pintype "power_in"))
      (node (ref "U88") (pin "6") (pinfunction "VDD1P0_6") (pintype "power_in"))
    )
    (net (code "53") (name "VDD_2V5") (class "Default")
      (node (ref "C194") (pin "1") (pinfunction "1_1") (pintype "passive"))
      (node (ref "C196") (pin "1") (pinfunction "1_1") (pintype "passive"))
      (node (ref "C199") (pin "1") (pinfunction "1_1") (pintype "passive"))
      (node (ref "C588") (pin "1") (pinfunction "1_1") (pintype "passive"))
      (node (ref "C592") (pin "1") (pinfunction "1_1") (pintype "passive"))
      (node (ref "U88") (pin "3") (pinfunction "VDDA2P5_3") (pintype "power_in"))
      (node (ref "U88") (pin "9") (pinfunction "VDDA2P5_9") (pintype "power_in"))
    )
    (net (code "54") (name "unconnected-(U88-JTAG_CLK-Pad20)") (class "Default")
      (node (ref "U88") (pin "20") (pinfunction "JTAG_CLK_20") (pintype "input+no_connect"))
    )
    (net (code "55") (name "unconnected-(U88-JTAG_TDI-Pad23)") (class "Default")
      (node (ref "U88") (pin "23") (pinfunction "JTAG_TDI_23") (pintype "input+no_connect"))
    )
    (net (code "56") (name "unconnected-(U88-JTAG_TDO-Pad21)") (class "Default")
      (node (ref "U88") (pin "21") (pinfunction "JTAG_TDO_21") (pintype "output+no_connect"))
    )
    (net (code "57") (name "unconnected-(U88-JTAG_TMS-Pad22)") (class "Default")
      (node (ref "U88") (pin "22") (pinfunction "JTAG_TMS_22") (pintype "bidirectional+no_connect"))
    )
    (net (code "58") (name "unconnected-(U88-XO-Pad14)") (class "Default")
      (node (ref "U88") (pin "14") (pinfunction "XO_14") (pintype "output+no_connect"))
    )
  )
)
